# HE.net
KiCad netlist of a schematic drawn in Altium Designer
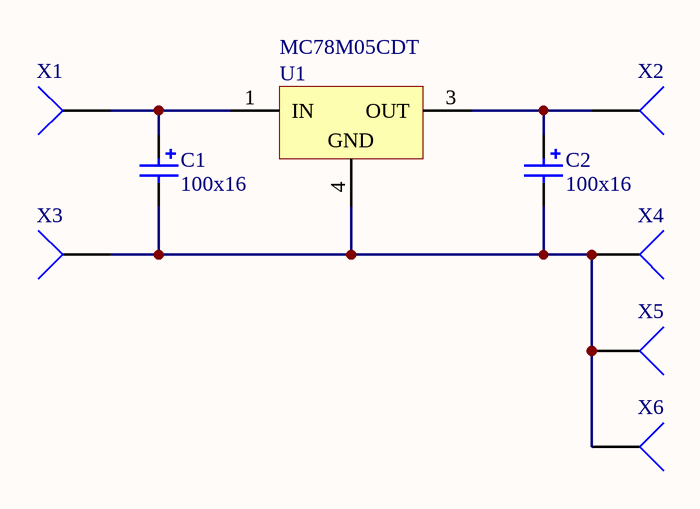
[diagram p0: HE.SchDoc]

(export (version "E")
  (design (tool "Eeschema 10.0.6"))
  (components
    (comp (ref "C1")
      (value "100x16")
      (footprint "el3")
      (description "Polarized Capacitor (Radial)")
      (fields (field (name "MANUFACTURER") "Generic Components") (field (name "PUBLISHER") "Altium Limited"))
      (libsource (lib "BUF") (part "Cap Pol"))
    )
    (comp (ref "C2")
      (value "100x16")
      (footprint "el3")
      (description "Polarized Capacitor (Radial)")
      (fields (field (name "MANUFACTURER") "Generic Components") (field (name "PUBLISHER") "Altium Limited"))
      (libsource (lib "BUF") (part "Cap Pol"))
    )
    (comp (ref "U1")
      (value "MC78M05CDT")
      (footprint "SIP-G3/C7")
      (description "3-Terminal Medium-Current Positive Fixed Voltage Regulator")
      (fields (field (name "MANUFACTURER") "Motorola") (field (name "PUBLISHER") "Altium Limited"))
      (libsource (lib "Motorola Power Management Voltage Regulator") (part "MC78M05CDT"))
    )
    (comp (ref "X1")
      (value "~")
      (footprint "PIN1")
      (description "Socket")
      (fields (field (name "MANUFACTURER") "Generic Components") (field (name "PUBLISHER") "Altium Limited"))
      (libsource (lib "Miscellaneous Connectors") (part "Socket"))
    )
    (comp (ref "X2")
      (value "~")
      (footprint "PIN1")
      (description "Socket")
      (fields (field (name "MANUFACTURER") "Generic Components") (field (name "PUBLISHER") "Altium Limited"))
      (libsource (lib "Miscellaneous Connectors") (part "Socket"))
    )
    (comp (ref "X3")
      (value "~")
      (footprint "PIN1")
      (description "Socket")
      (fields (field (name "MANUFACTURER") "Generic Components") (field (name "PUBLISHER") "Altium Limited"))
      (libsource (lib "Miscellaneous Connectors") (part "Socket"))
    )
    (comp (ref "X4")
      (value "~")
      (footprint "PIN1")
      (description "Socket")
      (fields (field (name "MANUFACTURER") "Generic Components") (field (name "PUBLISHER") "Altium Limited"))
      (libsource (lib "Miscellaneous Connectors") (part "Socket"))
    )
    (comp (ref "X5")
      (value "~")
      (footprint "PIN1")
      (description "Socket")
      (fields (field (name "MANUFACTURER") "Generic Components") (field (name "PUBLISHER") "Altium Limited"))
      (libsource (lib "Miscellaneous Connectors") (part "Socket"))
    )
    (comp (ref "X6")
      (value "~")
      (footprint "PIN1")
      (description "Socket")
      (fields (field (name "MANUFACTURER") "Generic Components") (field (name "PUBLISHER") "Altium Limited"))
      (libsource (lib "Miscellaneous Connectors") (part "Socket"))
    )
  )
  (nets
    (net (code "1") (name "Net-(U1-GND)") (class "Default")
      (node (ref "C1") (pin "2") (pinfunction "2_2") (pintype "passive"))
      (node (ref "C2") (pin "2") (pinfunction "2_2") (pintype "passive"))
      (node (ref "U1") (pin "4") (pinfunction "GND_4") (pintype "power_in"))
      (node (ref "X3") (pin "1") (pinfunction "1_1") (pintype "passive"))
      (node (ref "X4") (pin "1") (pinfunction "1_1") (pintype "passive"))
      (node (ref "X5") (pin "1") (pinfunction "1_1") (pintype "passive"))
      (node (ref "X6") (pin "1") (pinfunction "1_1") (pintype "passive"))
    )
    (net (code "2") (name "Net-(U1-IN)") (class "Default")
      (node (ref "C1") (pin "1") (pinfunction "1_1") (pintype "passive"))
      (node (ref "U1") (pin "1") (pinfunction "IN_1") (pintype "power_in"))
      (node (ref "X1") (pin "1") (pinfunction "1_1") (pintype "passive"))
    )
    (net (code "3") (name "Net-(U1-OUT)") (class "Default")
      (node (ref "C2") (pin "1") (pinfunction "1_1") (pintype "passive"))
      (node (ref "U1") (pin "3") (pinfunction "OUT_3") (pintype "power_in"))
      (node (ref "X2") (pin "1") (pinfunction "1_1") (pintype "passive"))
    )
  )
)
